# Deploy_Switches.net
KiCad netlist of a schematic drawn in Altium Designer
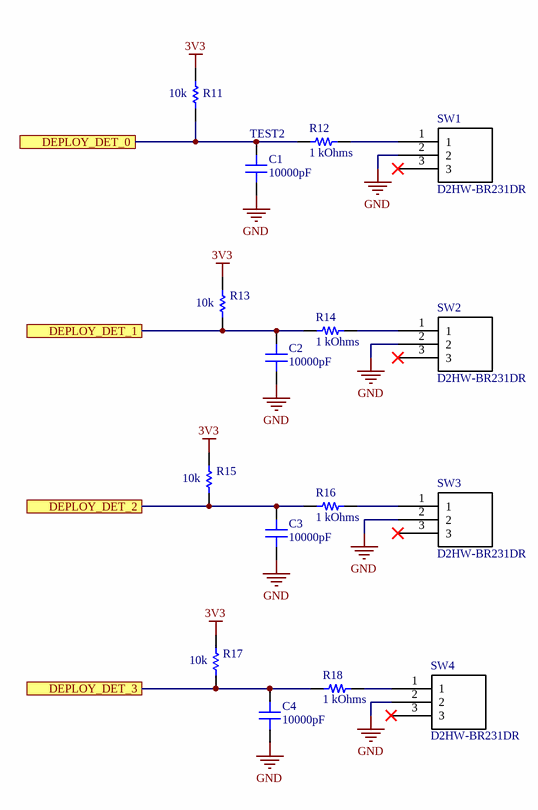
[diagram p0: Deploy_Switches.SchDoc]

(export (version "E")
  (design (tool "Eeschema 10.0.6"))
  (components
    (comp (ref "C1")
      (value "10000pF")
      (footprint "CAP 0603_1608")
      (description "CAP CER 10000PF 16V X7R 0603")
      (fields (field (name "PART NUMBER") "C0603S103K4RACTU") (field (name "MANUFACTURER") "KEMET"))
      (libsource (lib "Celestial Altium Library - altium_library") (part "Capacitor"))
    )
    (comp (ref "C2")
      (value "10000pF")
      (footprint "CAP 0603_1608")
      (description "CAP CER 10000PF 16V X7R 0603")
      (fields (field (name "PART NUMBER") "C0603S103K4RACTU") (field (name "MANUFACTURER") "KEMET"))
      (libsource (lib "Celestial Altium Library - altium_library") (part "Capacitor"))
    )
    (comp (ref "C3")
      (value "10000pF")
      (footprint "CAP 0603_1608")
      (description "CAP CER 10000PF 16V X7R 0603")
      (fields (field (name "PART NUMBER") "C0603S103K4RACTU") (field (name "MANUFACTURER") "KEMET"))
      (libsource (lib "Celestial Altium Library - altium_library") (part "Capacitor"))
    )
    (comp (ref "C4")
      (value "10000pF")
      (footprint "CAP 0603_1608")
      (description "CAP CER 10000PF 16V X7R 0603")
      (fields (field (name "PART NUMBER") "C0603S103K4RACTU") (field (name "MANUFACTURER") "KEMET"))
      (libsource (lib "Celestial Altium Library - altium_library") (part "Capacitor"))
    )
    (comp (ref "R11")
      (value "10k")
      (footprint "RES 0603_1608")
      (description "Chip Resistor, 10 KOhm, +/- 1%, 100 mW, -55 to 155 degC, 0603 (1608 Metric), RoHS, Tape and Reel")
      (fields (field (name "MANUFACTURER") "Vishay Semiconductor") (field (name "Comment") "1 kOhms"))
      (libsource (lib "Altium Content Vault") (part "RES-2"))
    )
    (comp (ref "R12")
      (value "1 kOhms")
      (footprint "RES 0603_1608")
      (description "RES SMD 1K OHM 0.1% 1/16W 0603")
      (fields
        (field (name "PART NUMBER") "CPF0603B1K0E")
        (field (name "MANUFACTURER") "TE Connectivity Passive Product")
      )
      (libsource (lib "Celestial Altium Library - altium_library") (part "Resistor"))
    )
    (comp (ref "R13")
      (value "10k")
      (footprint "RESC1609X50X30NL8T20")
      (description "Chip Resistor, 10 KOhm, +/- 1%, 100 mW, -55 to 155 degC, 0603 (1608 Metric), RoHS, Tape and Reel")
      (fields
        (field (name "MANUFACTURER") "Vishay Semiconductor")
        (field (name "Comment") "CRCW060310K0FKEA")
      )
      (libsource (lib "") (part "RES-2_1"))
    )
    (comp (ref "R14")
      (value "1 kOhms")
      (footprint "RES 0603_1608")
      (description "RES SMD 1K OHM 0.1% 1/16W 0603")
      (fields
        (field (name "PART NUMBER") "CPF0603B1K0E")
        (field (name "MANUFACTURER") "TE Connectivity Passive Product")
      )
      (libsource (lib "Celestial Altium Library - altium_library") (part "Resistor"))
    )
    (comp (ref "R15")
      (value "10k")
      (footprint "RES 0603_1608")
      (description "Chip Resistor, 10 KOhm, +/- 1%, 100 mW, -55 to 155 degC, 0603 (1608 Metric), RoHS, Tape and Reel")
      (fields (field (name "MANUFACTURER") "Vishay Semiconductor") (field (name "Comment") "1 kOhms"))
      (libsource (lib "Altium Content Vault") (part "RES-2"))
    )
    (comp (ref "R16")
      (value "1 kOhms")
      (footprint "RESC1609X50X30NL8T20")
      (description "RES SMD 1K OHM 0.1% 1/16W 0603")
      (fields
        (field (name "PART NUMBER") "CPF0603B1K0E")
        (field (name "MANUFACTURER") "TE Connectivity Passive Product")
      )
      (libsource (lib "Celestial Altium Library - altium_library") (part "Resistor"))
    )
    (comp (ref "R17")
      (value "10k")
      (footprint "RES 0603_1608")
      (description "Chip Resistor, 10 KOhm, +/- 1%, 100 mW, -55 to 155 degC, 0603 (1608 Metric), RoHS, Tape and Reel")
      (fields (field (name "MANUFACTURER") "Vishay Semiconductor") (field (name "Comment") "1 kOhms"))
      (libsource (lib "Altium Content Vault") (part "RES-2"))
    )
    (comp (ref "R18")
      (value "1 kOhms")
      (footprint "RESC1609X50X30NL8T20")
      (description "RES SMD 1K OHM 0.1% 1/16W 0603")
      (fields
        (field (name "PART NUMBER") "CPF0603B1K0E")
        (field (name "MANUFACTURER") "TE Connectivity Passive Product")
      )
      (libsource (lib "Celestial Altium Library - altium_library") (part "Resistor"))
    )
    (comp (ref "SW1") (value "D2HW-BR231DR") (libsource (lib "D2HW-BR231") (part "D2HW-BR231DR")))
    (comp (ref "SW2") (value "D2HW-BR231DR") (libsource (lib "D2HW-BR231") (part "D2HW-BR231DR")))
    (comp (ref "SW3") (value "D2HW-BR231DR") (libsource (lib "D2HW-BR231") (part "D2HW-BR231DR")))
    (comp (ref "SW4") (value "D2HW-BR231DR") (libsource (lib "D2HW-BR231") (part "D2HW-BR231DR")))
  )
  (nets
    (net (code "1") (name "/DEPLOY_DET_0") (class "Default")
      (node (ref "C1") (pin "2") (pinfunction "2_2") (pintype "passive"))
      (node (ref "R11") (pin "2") (pinfunction "2_2") (pintype "passive"))
      (node (ref "R12") (pin "1") (pinfunction "1_1") (pintype "passive"))
    )
    (net (code "2") (name "/DEPLOY_DET_1") (class "Default")
      (node (ref "C2") (pin "2") (pinfunction "2_2") (pintype "passive"))
      (node (ref "R13") (pin "1") (pinfunction "1_1") (pintype "passive"))
      (node (ref "R14") (pin "1") (pinfunction "1_1") (pintype "passive"))
    )
    (net (code "3") (name "/DEPLOY_DET_2") (class "Default")
      (node (ref "C3") (pin "2") (pinfunction "2_2") (pintype "passive"))
      (node (ref "R15") (pin "2") (pinfunction "2_2") (pintype "passive"))
      (node (ref "R16") (pin "1") (pinfunction "1_1") (pintype "passive"))
    )
    (net (code "4") (name "/DEPLOY_DET_3") (class "Default")
      (node (ref "C4") (pin "2") (pinfunction "2_2") (pintype "passive"))
      (node (ref "R17") (pin "2") (pinfunction "2_2") (pintype "passive"))
      (node (ref "R18") (pin "1") (pinfunction "1_1") (pintype "passive"))
    )
    (net (code "5") (name "3V3") (class "Default")
      (node (ref "R11") (pin "2") (pinfunction "2_2") (pintype "passive"))
      (node (ref "R13") (pin "2") (pinfunction "2_2") (pintype "passive"))
      (node (ref "R15") (pin "2") (pinfunction "2_2") (pintype "passive"))
      (node (ref "R17") (pin "2") (pinfunction "2_2") (pintype "passive"))
    )
    (net (code "6") (name "GND") (class "Default")
      (node (ref "C1") (pin "1") (pinfunction "1_1") (pintype "passive"))
      (node (ref "C2") (pin "1") (pinfunction "1_1") (pintype "passive"))
      (node (ref "C3") (pin "1") (pinfunction "1_1") (pintype "passive"))
      (node (ref "C4") (pin "1") (pinfunction "1_1") (pintype "passive"))
      (node (ref "SW1") (pin "2") (pinfunction "2_2") (pintype "passive"))
      (node (ref "SW2") (pin "2") (pinfunction "2_2") (pintype "passive"))
      (node (ref "SW3") (pin "2") (pinfunction "2_2") (pintype "passive"))
      (node (ref "SW4") (pin "2") (pinfunction "2_2") (pintype "passive"))
    )
    (net (code "7") (name "Net-(R12-Pad2)") (class "Default")
      (node (ref "R12") (pin "2") (pinfunction "2_2") (pintype "passive"))
      (node (ref "SW1") (pin "1") (pinfunction "1_1") (pintype "passive"))
    )
    (net (code "8") (name "Net-(R14-Pad2)") (class "Default")
      (node (ref "R14") (pin "2") (pinfunction "2_2") (pintype "passive"))
      (node (ref "SW2") (pin "1") (pinfunction "1_1") (pintype "passive"))
    )
    (net (code "9") (name "Net-(R16-Pad2)") (class "Default")
      (node (ref "R16") (pin "2") (pinfunction "2_2") (pintype "passive"))
      (node (ref "SW3") (pin "1") (pinfunction "1_1") (pintype "passive"))
    )
    (net (code "10") (name "Net-(R18-Pad2)") (class "Default")
      (node (ref "R18") (pin "2") (pinfunction "2_2") (pintype "passive"))
      (node (ref "SW4") (pin "1") (pinfunction "1_1") (pintype "passive"))
    )
    (net (code "11") (name "unconnected-(SW1-Pad3)") (class "Default")
      (node (ref "SW1") (pin "3") (pinfunction "3_3") (pintype "passive+no_connect"))
    )
    (net (code "12") (name "unconnected-(SW2-Pad3)") (class "Default")
      (node (ref "SW2") (pin "3") (pinfunction "3_3") (pintype "passive+no_connect"))
    )
    (net (code "13") (name "unconnected-(SW3-Pad3)") (class "Default")
      (node (ref "SW3") (pin "3") (pinfunction "3_3") (pintype "passive+no_connect"))
    )
    (net (code "14") (name "unconnected-(SW4-Pad3)") (class "Default")
      (node (ref "SW4") (pin "3") (pinfunction "3_3") (pintype "passive+no_connect"))
    )
  )
)
